# display_zm1325_rev_a.net
KiCad netlist of a schematic drawn in EAGLE
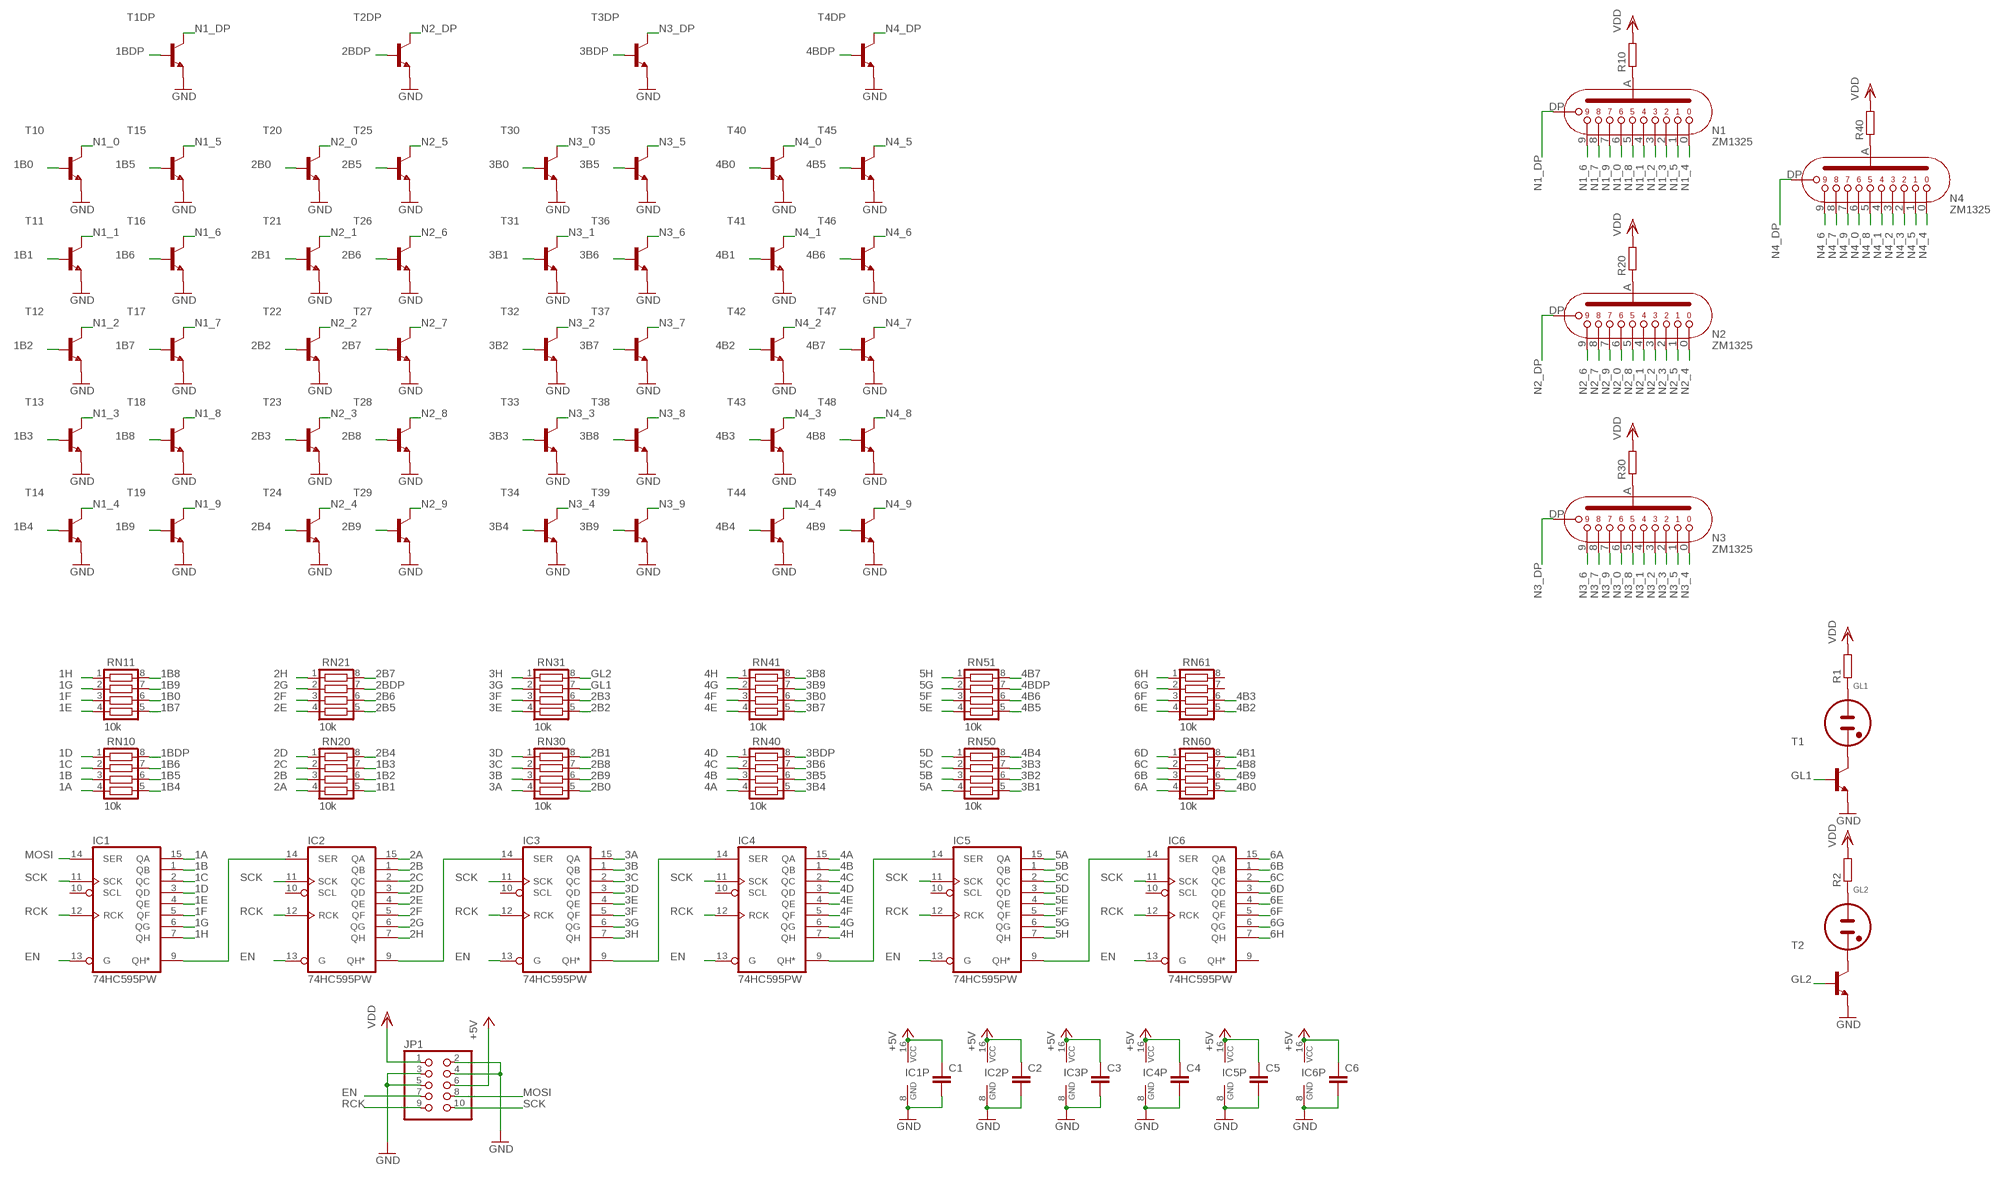
[diagram p0: schematic, sheet 1]

(export (version "E")
  (design (tool "Eeschema 10.0.6"))
  (components
    (comp (ref "C1")
      (value "C-EUC0603")
      (footprint "eagle-import:C0603")
      (libsource (lib "eagle-import") (part "C-EUC0603"))
    )
    (comp (ref "C2")
      (value "C-EUC0603")
      (footprint "eagle-import:C0603")
      (libsource (lib "eagle-import") (part "C-EUC0603"))
    )
    (comp (ref "C3")
      (value "C-EUC0603")
      (footprint "eagle-import:C0603")
      (libsource (lib "eagle-import") (part "C-EUC0603"))
    )
    (comp (ref "C4")
      (value "C-EUC0603")
      (footprint "eagle-import:C0603")
      (libsource (lib "eagle-import") (part "C-EUC0603"))
    )
    (comp (ref "C5")
      (value "C-EUC0603")
      (footprint "eagle-import:C0603")
      (libsource (lib "eagle-import") (part "C-EUC0603"))
    )
    (comp (ref "C6")
      (value "C-EUC0603")
      (footprint "eagle-import:C0603")
      (libsource (lib "eagle-import") (part "C-EUC0603"))
    )
    (comp (ref "GL1")
      (value "NE2-NEON-BULB-DRILL")
      (footprint "eagle-import:NE2-NEON-BULB-DRILL")
      (libsource (lib "eagle-import") (part "NE2-NEON-BULB-DRILL"))
    )
    (comp (ref "GL2")
      (value "NE2-NEON-BULB-DRILL")
      (footprint "eagle-import:NE2-NEON-BULB-DRILL")
      (libsource (lib "eagle-import") (part "NE2-NEON-BULB-DRILL"))
    )
    (comp (ref "IC1")
      (value "74HC595PW")
      (footprint "eagle-import:TSSOP16")
      (libsource (lib "eagle-import") (part "74595PWHC"))
    )
    (comp (ref "IC2")
      (value "74HC595PW")
      (footprint "eagle-import:TSSOP16")
      (libsource (lib "eagle-import") (part "74595PWHC"))
    )
    (comp (ref "IC3")
      (value "74HC595PW")
      (footprint "eagle-import:TSSOP16")
      (libsource (lib "eagle-import") (part "74595PWHC"))
    )
    (comp (ref "IC4")
      (value "74HC595PW")
      (footprint "eagle-import:TSSOP16")
      (libsource (lib "eagle-import") (part "74595PWHC"))
    )
    (comp (ref "IC5")
      (value "74HC595PW")
      (footprint "eagle-import:TSSOP16")
      (libsource (lib "eagle-import") (part "74595PWHC"))
    )
    (comp (ref "IC6")
      (value "74HC595PW")
      (footprint "eagle-import:TSSOP16")
      (libsource (lib "eagle-import") (part "74595PWHC"))
    )
    (comp (ref "JP1")
      (value "PINHD-2X5_2.54-SMD")
      (footprint "eagle-import:2X05SMD")
      (libsource (lib "eagle-import") (part "PINHD-2X5_2.54-SMD"))
    )
    (comp (ref "N1")
      (value "ZM1325")
      (footprint "eagle-import:ZM1325")
      (libsource (lib "eagle-import") (part "ZM1325"))
    )
    (comp (ref "N2")
      (value "ZM1325")
      (footprint "eagle-import:ZM1325")
      (libsource (lib "eagle-import") (part "ZM1325"))
    )
    (comp (ref "N3")
      (value "ZM1325")
      (footprint "eagle-import:ZM1325")
      (libsource (lib "eagle-import") (part "ZM1325"))
    )
    (comp (ref "N4")
      (value "ZM1325")
      (footprint "eagle-import:ZM1325")
      (libsource (lib "eagle-import") (part "ZM1325"))
    )
    (comp (ref "R1")
      (value "R-EU_R0603")
      (footprint "eagle-import:R0603")
      (libsource (lib "eagle-import") (part "R-EU_R0603"))
    )
    (comp (ref "R2")
      (value "R-EU_R0603")
      (footprint "eagle-import:R0603")
      (libsource (lib "eagle-import") (part "R-EU_R0603"))
    )
    (comp (ref "R10")
      (value "R-EU_R0603")
      (footprint "eagle-import:R0603")
      (libsource (lib "eagle-import") (part "R-EU_R0603"))
    )
    (comp (ref "R20")
      (value "R-EU_R0603")
      (footprint "eagle-import:R0603")
      (libsource (lib "eagle-import") (part "R-EU_R0603"))
    )
    (comp (ref "R30")
      (value "R-EU_R0603")
      (footprint "eagle-import:R0603")
      (libsource (lib "eagle-import") (part "R-EU_R0603"))
    )
    (comp (ref "R40")
      (value "R-EU_R0603")
      (footprint "eagle-import:R0603")
      (libsource (lib "eagle-import") (part "R-EU_R0603"))
    )
    (comp (ref "RN10")
      (value "10k")
      (footprint "eagle-import:CTS742C083")
      (fields (field (name "OC_FARNELL") "unknown") (field (name "OC_NEWARK") "unknown"))
      (libsource (lib "eagle-import") (part "CTS742C083"))
    )
    (comp (ref "RN11")
      (value "10k")
      (footprint "eagle-import:CTS742C083")
      (fields (field (name "OC_FARNELL") "unknown") (field (name "OC_NEWARK") "unknown"))
      (libsource (lib "eagle-import") (part "CTS742C083"))
    )
    (comp (ref "RN20")
      (value "10k")
      (footprint "eagle-import:CTS742C083")
      (fields (field (name "OC_FARNELL") "unknown") (field (name "OC_NEWARK") "unknown"))
      (libsource (lib "eagle-import") (part "CTS742C083"))
    )
    (comp (ref "RN21")
      (value "10k")
      (footprint "eagle-import:CTS742C083")
      (fields (field (name "OC_FARNELL") "unknown") (field (name "OC_NEWARK") "unknown"))
      (libsource (lib "eagle-import") (part "CTS742C083"))
    )
    (comp (ref "RN30")
      (value "10k")
      (footprint "eagle-import:CTS742C083")
      (fields (field (name "OC_FARNELL") "unknown") (field (name "OC_NEWARK") "unknown"))
      (libsource (lib "eagle-import") (part "CTS742C083"))
    )
    (comp (ref "RN31")
      (value "10k")
      (footprint "eagle-import:CTS742C083")
      (fields (field (name "OC_FARNELL") "unknown") (field (name "OC_NEWARK") "unknown"))
      (libsource (lib "eagle-import") (part "CTS742C083"))
    )
    (comp (ref "RN40")
      (value "10k")
      (footprint "eagle-import:CTS742C083")
      (fields (field (name "OC_FARNELL") "unknown") (field (name "OC_NEWARK") "unknown"))
      (libsource (lib "eagle-import") (part "CTS742C083"))
    )
    (comp (ref "RN41")
      (value "10k")
      (footprint "eagle-import:CTS742C083")
      (fields (field (name "OC_FARNELL") "unknown") (field (name "OC_NEWARK") "unknown"))
      (libsource (lib "eagle-import") (part "CTS742C083"))
    )
    (comp (ref "RN50")
      (value "10k")
      (footprint "eagle-import:CTS742C083")
      (fields (field (name "OC_FARNELL") "unknown") (field (name "OC_NEWARK") "unknown"))
      (libsource (lib "eagle-import") (part "CTS742C083"))
    )
    (comp (ref "RN51")
      (value "10k")
      (footprint "eagle-import:CTS742C083")
      (fields (field (name "OC_FARNELL") "unknown") (field (name "OC_NEWARK") "unknown"))
      (libsource (lib "eagle-import") (part "CTS742C083"))
    )
    (comp (ref "RN60")
      (value "10k")
      (footprint "eagle-import:CTS742C083")
      (fields (field (name "OC_FARNELL") "unknown") (field (name "OC_NEWARK") "unknown"))
      (libsource (lib "eagle-import") (part "CTS742C083"))
    )
    (comp (ref "RN61")
      (value "10k")
      (footprint "eagle-import:CTS742C083")
      (fields (field (name "OC_FARNELL") "unknown") (field (name "OC_NEWARK") "unknown"))
      (libsource (lib "eagle-import") (part "CTS742C083"))
    )
    (comp (ref "T1")
      (value "SMBTA42")
      (footprint "eagle-import:SOT23")
      (libsource (lib "eagle-import") (part "SMBTA42"))
    )
    (comp (ref "T1DP")
      (value "SMBTA42")
      (footprint "eagle-import:SOT23")
      (libsource (lib "eagle-import") (part "SMBTA42"))
    )
    (comp (ref "T2")
      (value "SMBTA42")
      (footprint "eagle-import:SOT23")
      (libsource (lib "eagle-import") (part "SMBTA42"))
    )
    (comp (ref "T2DP")
      (value "SMBTA42")
      (footprint "eagle-import:SOT23")
      (libsource (lib "eagle-import") (part "SMBTA42"))
    )
    (comp (ref "T3DP")
      (value "SMBTA42")
      (footprint "eagle-import:SOT23")
      (libsource (lib "eagle-import") (part "SMBTA42"))
    )
    (comp (ref "T4DP")
      (value "SMBTA42")
      (footprint "eagle-import:SOT23")
      (libsource (lib "eagle-import") (part "SMBTA42"))
    )
    (comp (ref "T10")
      (value "SMBTA42")
      (footprint "eagle-import:SOT23")
      (libsource (lib "eagle-import") (part "SMBTA42"))
    )
    (comp (ref "T11")
      (value "SMBTA42")
      (footprint "eagle-import:SOT23")
      (libsource (lib "eagle-import") (part "SMBTA42"))
    )
    (comp (ref "T12")
      (value "SMBTA42")
      (footprint "eagle-import:SOT23")
      (libsource (lib "eagle-import") (part "SMBTA42"))
    )
    (comp (ref "T13")
      (value "SMBTA42")
      (footprint "eagle-import:SOT23")
      (libsource (lib "eagle-import") (part "SMBTA42"))
    )
    (comp (ref "T14")
      (value "SMBTA42")
      (footprint "eagle-import:SOT23")
      (libsource (lib "eagle-import") (part "SMBTA42"))
    )
    (comp (ref "T15")
      (value "SMBTA42")
      (footprint "eagle-import:SOT23")
      (libsource (lib "eagle-import") (part "SMBTA42"))
    )
    (comp (ref "T16")
      (value "SMBTA42")
      (footprint "eagle-import:SOT23")
      (libsource (lib "eagle-import") (part "SMBTA42"))
    )
    (comp (ref "T17")
      (value "SMBTA42")
      (footprint "eagle-import:SOT23")
      (libsource (lib "eagle-import") (part "SMBTA42"))
    )
    (comp (ref "T18")
      (value "SMBTA42")
      (footprint "eagle-import:SOT23")
      (libsource (lib "eagle-import") (part "SMBTA42"))
    )
    (comp (ref "T19")
      (value "SMBTA42")
      (footprint "eagle-import:SOT23")
      (libsource (lib "eagle-import") (part "SMBTA42"))
    )
    (comp (ref "T20")
      (value "SMBTA42")
      (footprint "eagle-import:SOT23")
      (libsource (lib "eagle-import") (part "SMBTA42"))
    )
    (comp (ref "T21")
      (value "SMBTA42")
      (footprint "eagle-import:SOT23")
      (libsource (lib "eagle-import") (part "SMBTA42"))
    )
    (comp (ref "T22")
      (value "SMBTA42")
      (footprint "eagle-import:SOT23")
      (libsource (lib "eagle-import") (part "SMBTA42"))
    )
    (comp (ref "T23")
      (value "SMBTA42")
      (footprint "eagle-import:SOT23")
      (libsource (lib "eagle-import") (part "SMBTA42"))
    )
    (comp (ref "T24")
      (value "SMBTA42")
      (footprint "eagle-import:SOT23")
      (libsource (lib "eagle-import") (part "SMBTA42"))
    )
    (comp (ref "T25")
      (value "SMBTA42")
      (footprint "eagle-import:SOT23")
      (libsource (lib "eagle-import") (part "SMBTA42"))
    )
    (comp (ref "T26")
      (value "SMBTA42")
      (footprint "eagle-import:SOT23")
      (libsource (lib "eagle-import") (part "SMBTA42"))
    )
    (comp (ref "T27")
      (value "SMBTA42")
      (footprint "eagle-import:SOT23")
      (libsource (lib "eagle-import") (part "SMBTA42"))
    )
    (comp (ref "T28")
      (value "SMBTA42")
      (footprint "eagle-import:SOT23")
      (libsource (lib "eagle-import") (part "SMBTA42"))
    )
    (comp (ref "T29")
      (value "SMBTA42")
      (footprint "eagle-import:SOT23")
      (libsource (lib "eagle-import") (part "SMBTA42"))
    )
    (comp (ref "T30")
      (value "SMBTA42")
      (footprint "eagle-import:SOT23")
      (libsource (lib "eagle-import") (part "SMBTA42"))
    )
    (comp (ref "T31")
      (value "SMBTA42")
      (footprint "eagle-import:SOT23")
      (libsource (lib "eagle-import") (part "SMBTA42"))
    )
    (comp (ref "T32")
      (value "SMBTA42")
      (footprint "eagle-import:SOT23")
      (libsource (lib "eagle-import") (part "SMBTA42"))
    )
    (comp (ref "T33")
      (value "SMBTA42")
      (footprint "eagle-import:SOT23")
      (libsource (lib "eagle-import") (part "SMBTA42"))
    )
    (comp (ref "T34")
      (value "SMBTA42")
      (footprint "eagle-import:SOT23")
      (libsource (lib "eagle-import") (part "SMBTA42"))
    )
    (comp (ref "T35")
      (value "SMBTA42")
      (footprint "eagle-import:SOT23")
      (libsource (lib "eagle-import") (part "SMBTA42"))
    )
    (comp (ref "T36")
      (value "SMBTA42")
      (footprint "eagle-import:SOT23")
      (libsource (lib "eagle-import") (part "SMBTA42"))
    )
    (comp (ref "T37")
      (value "SMBTA42")
      (footprint "eagle-import:SOT23")
      (libsource (lib "eagle-import") (part "SMBTA42"))
    )
    (comp (ref "T38")
      (value "SMBTA42")
      (footprint "eagle-import:SOT23")
      (libsource (lib "eagle-import") (part "SMBTA42"))
    )
    (comp (ref "T39")
      (value "SMBTA42")
      (footprint "eagle-import:SOT23")
      (libsource (lib "eagle-import") (part "SMBTA42"))
    )
    (comp (ref "T40")
      (value "SMBTA42")
      (footprint "eagle-import:SOT23")
      (libsource (lib "eagle-import") (part "SMBTA42"))
    )
    (comp (ref "T41")
      (value "SMBTA42")
      (footprint "eagle-import:SOT23")
      (libsource (lib "eagle-import") (part "SMBTA42"))
    )
    (comp (ref "T42")
      (value "SMBTA42")
      (footprint "eagle-import:SOT23")
      (libsource (lib "eagle-import") (part "SMBTA42"))
    )
    (comp (ref "T43")
      (value "SMBTA42")
      (footprint "eagle-import:SOT23")
      (libsource (lib "eagle-import") (part "SMBTA42"))
    )
    (comp (ref "T44")
      (value "SMBTA42")
      (footprint "eagle-import:SOT23")
      (libsource (lib "eagle-import") (part "SMBTA42"))
    )
    (comp (ref "T45")
      (value "SMBTA42")
      (footprint "eagle-import:SOT23")
      (libsource (lib "eagle-import") (part "SMBTA42"))
    )
    (comp (ref "T46")
      (value "SMBTA42")
      (footprint "eagle-import:SOT23")
      (libsource (lib "eagle-import") (part "SMBTA42"))
    )
    (comp (ref "T47")
      (value "SMBTA42")
      (footprint "eagle-import:SOT23")
      (libsource (lib "eagle-import") (part "SMBTA42"))
    )
    (comp (ref "T48")
      (value "SMBTA42")
      (footprint "eagle-import:SOT23")
      (libsource (lib "eagle-import") (part "SMBTA42"))
    )
    (comp (ref "T49")
      (value "SMBTA42")
      (footprint "eagle-import:SOT23")
      (libsource (lib "eagle-import") (part "SMBTA42"))
    )
  )
  (nets
    (net (code "1") (name "+5V") (class "Default")
      (node (ref "C1") (pin "1") (pinfunction "1_1") (pintype "passive"))
      (node (ref "C2") (pin "1") (pinfunction "1_1") (pintype "passive"))
      (node (ref "C3") (pin "1") (pinfunction "1_1") (pintype "passive"))
      (node (ref "C4") (pin "1") (pinfunction "1_1") (pintype "passive"))
      (node (ref "C5") (pin "1") (pinfunction "1_1") (pintype "passive"))
      (node (ref "C6") (pin "1") (pinfunction "1_1") (pintype "passive"))
      (node (ref "IC1") (pin "16") (pinfunction "VCC_16") (pintype "power_in"))
      (node (ref "IC2") (pin "16") (pinfunction "VCC_16") (pintype "power_in"))
      (node (ref "IC3") (pin "16") (pinfunction "VCC_16") (pintype "power_in"))
      (node (ref "IC4") (pin "16") (pinfunction "VCC_16") (pintype "power_in"))
      (node (ref "IC5") (pin "16") (pinfunction "VCC_16") (pintype "power_in"))
      (node (ref "IC6") (pin "16") (pinfunction "VCC_16") (pintype "power_in"))
      (node (ref "JP1") (pin "6") (pinfunction "6_6") (pintype "passive"))
    )
    (net (code "2") (name "/1A") (class "Default")
      (node (ref "IC1") (pin "15") (pinfunction "QA_15") (pintype "tri_state"))
      (node (ref "RN10") (pin "4") (pinfunction "4_4") (pintype "passive"))
    )
    (net (code "3") (name "/1B") (class "Default")
      (node (ref "IC1") (pin "1") (pinfunction "QB_1") (pintype "tri_state"))
      (node (ref "RN10") (pin "3") (pinfunction "3_3") (pintype "passive"))
    )
    (net (code "4") (name "/1B0") (class "Default")
      (node (ref "RN11") (pin "6") (pinfunction "6_6") (pintype "passive"))
      (node (ref "T10") (pin "1") (pinfunction "B_1") (pintype "passive"))
    )
    (net (code "5") (name "/1B1") (class "Default")
      (node (ref "RN20") (pin "5") (pinfunction "5_5") (pintype "passive"))
      (node (ref "T11") (pin "1") (pinfunction "B_1") (pintype "passive"))
    )
    (net (code "6") (name "/1B2") (class "Default")
      (node (ref "RN20") (pin "6") (pinfunction "6_6") (pintype "passive"))
      (node (ref "T12") (pin "1") (pinfunction "B_1") (pintype "passive"))
    )
    (net (code "7") (name "/1B3") (class "Default")
      (node (ref "RN20") (pin "7") (pinfunction "7_7") (pintype "passive"))
      (node (ref "T13") (pin "1") (pinfunction "B_1") (pintype "passive"))
    )
    (net (code "8") (name "/1B4") (class "Default")
      (node (ref "RN10") (pin "5") (pinfunction "5_5") (pintype "passive"))
      (node (ref "T14") (pin "1") (pinfunction "B_1") (pintype "passive"))
    )
    (net (code "9") (name "/1B5") (class "Default")
      (node (ref "RN10") (pin "6") (pinfunction "6_6") (pintype "passive"))
      (node (ref "T15") (pin "1") (pinfunction "B_1") (pintype "passive"))
    )
    (net (code "10") (name "/1B6") (class "Default")
      (node (ref "RN10") (pin "7") (pinfunction "7_7") (pintype "passive"))
      (node (ref "T16") (pin "1") (pinfunction "B_1") (pintype "passive"))
    )
    (net (code "11") (name "/1B7") (class "Default")
      (node (ref "RN11") (pin "5") (pinfunction "5_5") (pintype "passive"))
      (node (ref "T17") (pin "1") (pinfunction "B_1") (pintype "passive"))
    )
    (net (code "12") (name "/1B8") (class "Default")
      (node (ref "RN11") (pin "8") (pinfunction "8_8") (pintype "passive"))
      (node (ref "T18") (pin "1") (pinfunction "B_1") (pintype "passive"))
    )
    (net (code "13") (name "/1B9") (class "Default")
      (node (ref "RN11") (pin "7") (pinfunction "7_7") (pintype "passive"))
      (node (ref "T19") (pin "1") (pinfunction "B_1") (pintype "passive"))
    )
    (net (code "14") (name "/1BDP") (class "Default")
      (node (ref "RN10") (pin "8") (pinfunction "8_8") (pintype "passive"))
      (node (ref "T1DP") (pin "1") (pinfunction "B_1") (pintype "passive"))
    )
    (net (code "15") (name "/1C") (class "Default")
      (node (ref "IC1") (pin "2") (pinfunction "QC_2") (pintype "tri_state"))
      (node (ref "RN10") (pin "2") (pinfunction "2_2") (pintype "passive"))
    )
    (net (code "16") (name "/1D") (class "Default")
      (node (ref "IC1") (pin "3") (pinfunction "QD_3") (pintype "tri_state"))
      (node (ref "RN10") (pin "1") (pinfunction "1_1") (pintype "passive"))
    )
    (net (code "17") (name "/1E") (class "Default")
      (node (ref "IC1") (pin "4") (pinfunction "QE_4") (pintype "tri_state"))
      (node (ref "RN11") (pin "4") (pinfunction "4_4") (pintype "passive"))
    )
    (net (code "18") (name "/1F") (class "Default")
      (node (ref "IC1") (pin "5") (pinfunction "QF_5") (pintype "tri_state"))
      (node (ref "RN11") (pin "3") (pinfunction "3_3") (pintype "passive"))
    )
    (net (code "19") (name "/1G") (class "Default")
      (node (ref "IC1") (pin "6") (pinfunction "QG_6") (pintype "tri_state"))
      (node (ref "RN11") (pin "2") (pinfunction "2_2") (pintype "passive"))
    )
    (net (code "20") (name "/1H") (class "Default")
      (node (ref "IC1") (pin "7") (pinfunction "QH_7") (pintype "tri_state"))
      (node (ref "RN11") (pin "1") (pinfunction "1_1") (pintype "passive"))
    )
    (net (code "21") (name "/2A") (class "Default")
      (node (ref "IC2") (pin "15") (pinfunction "QA_15") (pintype "tri_state"))
      (node (ref "RN20") (pin "4") (pinfunction "4_4") (pintype "passive"))
    )
    (net (code "22") (name "/2B") (class "Default")
      (node (ref "IC2") (pin "1") (pinfunction "QB_1") (pintype "tri_state"))
      (node (ref "RN20") (pin "3") (pinfunction "3_3") (pintype "passive"))
    )
    (net (code "23") (name "/2B0") (class "Default")
      (node (ref "RN30") (pin "5") (pinfunction "5_5") (pintype "passive"))
      (node (ref "T20") (pin "1") (pinfunction "B_1") (pintype "passive"))
    )
    (net (code "24") (name "/2B1") (class "Default")
      (node (ref "RN30") (pin "8") (pinfunction "8_8") (pintype "passive"))
      (node (ref "T21") (pin "1") (pinfunction "B_1") (pintype "passive"))
    )
    (net (code "25") (name "/2B2") (class "Default")
      (node (ref "RN31") (pin "5") (pinfunction "5_5") (pintype "passive"))
      (node (ref "T22") (pin "1") (pinfunction "B_1") (pintype "passive"))
    )
    (net (code "26") (name "/2B3") (class "Default")
      (node (ref "RN31") (pin "6") (pinfunction "6_6") (pintype "passive"))
      (node (ref "T23") (pin "1") (pinfunction "B_1") (pintype "passive"))
    )
    (net (code "27") (name "/2B4") (class "Default")
      (node (ref "RN20") (pin "8") (pinfunction "8_8") (pintype "passive"))
      (node (ref "T24") (pin "1") (pinfunction "B_1") (pintype "passive"))
    )
    (net (code "28") (name "/2B5") (class "Default")
      (node (ref "RN21") (pin "5") (pinfunction "5_5") (pintype "passive"))
      (node (ref "T25") (pin "1") (pinfunction "B_1") (pintype "passive"))
    )
    (net (code "29") (name "/2B6") (class "Default")
      (node (ref "RN21") (pin "6") (pinfunction "6_6") (pintype "passive"))
      (node (ref "T26") (pin "1") (pinfunction "B_1") (pintype "passive"))
    )
    (net (code "30") (name "/2B7") (class "Default")
      (node (ref "RN21") (pin "8") (pinfunction "8_8") (pintype "passive"))
      (node (ref "T27") (pin "1") (pinfunction "B_1") (pintype "passive"))
    )
    (net (code "31") (name "/2B8") (class "Default")
      (node (ref "RN30") (pin "7") (pinfunction "7_7") (pintype "passive"))
      (node (ref "T28") (pin "1") (pinfunction "B_1") (pintype "passive"))
    )
    (net (code "32") (name "/2B9") (class "Default")
      (node (ref "RN30") (pin "6") (pinfunction "6_6") (pintype "passive"))
      (node (ref "T29") (pin "1") (pinfunction "B_1") (pintype "passive"))
    )
    (net (code "33") (name "/2BDP") (class "Default")
      (node (ref "RN21") (pin "7") (pinfunction "7_7") (pintype "passive"))
      (node (ref "T2DP") (pin "1") (pinfunction "B_1") (pintype "passive"))
    )
    (net (code "34") (name "/2C") (class "Default")
      (node (ref "IC2") (pin "2") (pinfunction "QC_2") (pintype "tri_state"))
      (node (ref "RN20") (pin "2") (pinfunction "2_2") (pintype "passive"))
    )
    (net (code "35") (name "/2D") (class "Default")
      (node (ref "IC2") (pin "3") (pinfunction "QD_3") (pintype "tri_state"))
      (node (ref "RN20") (pin "1") (pinfunction "1_1") (pintype "passive"))
    )
    (net (code "36") (name "/2E") (class "Default")
      (node (ref "IC2") (pin "4") (pinfunction "QE_4") (pintype "tri_state"))
      (node (ref "RN21") (pin "4") (pinfunction "4_4") (pintype "passive"))
    )
    (net (code "37") (name "/2F") (class "Default")
      (node (ref "IC2") (pin "5") (pinfunction "QF_5") (pintype "tri_state"))
      (node (ref "RN21") (pin "3") (pinfunction "3_3") (pintype "passive"))
    )
    (net (code "38") (name "/2G") (class "Default")
      (node (ref "IC2") (pin "6") (pinfunction "QG_6") (pintype "tri_state"))
      (node (ref "RN21") (pin "2") (pinfunction "2_2") (pintype "passive"))
    )
    (net (code "39") (name "/2H") (class "Default")
      (node (ref "IC2") (pin "7") (pinfunction "QH_7") (pintype "tri_state"))
      (node (ref "RN21") (pin "1") (pinfunction "1_1") (pintype "passive"))
    )
    (net (code "40") (name "/3A") (class "Default")
      (node (ref "IC3") (pin "15") (pinfunction "QA_15") (pintype "tri_state"))
      (node (ref "RN30") (pin "4") (pinfunction "4_4") (pintype "passive"))
    )
    (net (code "41") (name "/3B") (class "Default")
      (node (ref "IC3") (pin "1") (pinfunction "QB_1") (pintype "tri_state"))
      (node (ref "RN30") (pin "3") (pinfunction "3_3") (pintype "passive"))
    )
    (net (code "42") (name "/3B0") (class "Default")
      (node (ref "RN41") (pin "6") (pinfunction "6_6") (pintype "passive"))
      (node (ref "T30") (pin "1") (pinfunction "B_1") (pintype "passive"))
    )
    (net (code "43") (name "/3B1") (class "Default")
      (node (ref "RN50") (pin "5") (pinfunction "5_5") (pintype "passive"))
      (node (ref "T31") (pin "1") (pinfunction "B_1") (pintype "passive"))
    )
    (net (code "44") (name "/3B2") (class "Default")
      (node (ref "RN50") (pin "6") (pinfunction "6_6") (pintype "passive"))
      (node (ref "T32") (pin "1") (pinfunction "B_1") (pintype "passive"))
    )
    (net (code "45") (name "/3B3") (class "Default")
      (node (ref "RN50") (pin "7") (pinfunction "7_7") (pintype "passive"))
      (node (ref "T33") (pin "1") (pinfunction "B_1") (pintype "passive"))
    )
    (net (code "46") (name "/3B4") (class "Default")
      (node (ref "RN40") (pin "5") (pinfunction "5_5") (pintype "passive"))
      (node (ref "T34") (pin "1") (pinfunction "B_1") (pintype "passive"))
    )
    (net (code "47") (name "/3B5") (class "Default")
      (node (ref "RN40") (pin "6") (pinfunction "6_6") (pintype "passive"))
      (node (ref "T35") (pin "1") (pinfunction "B_1") (pintype "passive"))
    )
    (net (code "48") (name "/3B6") (class "Default")
      (node (ref "RN40") (pin "7") (pinfunction "7_7") (pintype "passive"))
      (node (ref "T36") (pin "1") (pinfunction "B_1") (pintype "passive"))
    )
    (net (code "49") (name "/3B7") (class "Default")
      (node (ref "RN41") (pin "5") (pinfunction "5_5") (pintype "passive"))
      (node (ref "T37") (pin "1") (pinfunction "B_1") (pintype "passive"))
    )
    (net (code "50") (name "/3B8") (class "Default")
      (node (ref "RN41") (pin "8") (pinfunction "8_8") (pintype "passive"))
      (node (ref "T38") (pin "1") (pinfunction "B_1") (pintype "passive"))
    )
    (net (code "51") (name "/3B9") (class "Default")
      (node (ref "RN41") (pin "7") (pinfunction "7_7") (pintype "passive"))
      (node (ref "T39") (pin "1") (pinfunction "B_1") (pintype "passive"))
    )
    (net (code "52") (name "/3BDP") (class "Default")
      (node (ref "RN40") (pin "8") (pinfunction "8_8") (pintype "passive"))
      (node (ref "T3DP") (pin "1") (pinfunction "B_1") (pintype "passive"))
    )
    (net (code "53") (name "/3C") (class "Default")
      (node (ref "IC3") (pin "2") (pinfunction "QC_2") (pintype "tri_state"))
      (node (ref "RN30") (pin "2") (pinfunction "2_2") (pintype "passive"))
    )
    (net (code "54") (name "/3D") (class "Default")
      (node (ref "IC3") (pin "3") (pinfunction "QD_3") (pintype "tri_state"))
      (node (ref "RN30") (pin "1") (pinfunction "1_1") (pintype "passive"))
    )
    (net (code "55") (name "/3E") (class "Default")
      (node (ref "IC3") (pin "4") (pinfunction "QE_4") (pintype "tri_state"))
      (node (ref "RN31") (pin "4") (pinfunction "4_4") (pintype "passive"))
    )
    (net (code "56") (name "/3F") (class "Default")
      (node (ref "IC3") (pin "5") (pinfunction "QF_5") (pintype "tri_state"))
      (node (ref "RN31") (pin "3") (pinfunction "3_3") (pintype "passive"))
    )
    (net (code "57") (name "/3G") (class "Default")
      (node (ref "IC3") (pin "6") (pinfunction "QG_6") (pintype "tri_state"))
      (node (ref "RN31") (pin "2") (pinfunction "2_2") (pintype "passive"))
    )
    (net (code "58") (name "/3H") (class "Default")
      (node (ref "IC3") (pin "7") (pinfunction "QH_7") (pintype "tri_state"))
      (node (ref "RN31") (pin "1") (pinfunction "1_1") (pintype "passive"))
    )
    (net (code "59") (name "/4A") (class "Default")
      (node (ref "IC4") (pin "15") (pinfunction "QA_15") (pintype "tri_state"))
      (node (ref "RN40") (pin "4") (pinfunction "4_4") (pintype "passive"))
    )
    (net (code "60") (name "/4B") (class "Default")
      (node (ref "IC4") (pin "1") (pinfunction "QB_1") (pintype "tri_state"))
      (node (ref "RN40") (pin "3") (pinfunction "3_3") (pintype "passive"))
    )
    (net (code "61") (name "/4B0") (class "Default")
      (node (ref "RN60") (pin "5") (pinfunction "5_5") (pintype "passive"))
      (node (ref "T40") (pin "1") (pinfunction "B_1") (pintype "passive"))
    )
    (net (code "62") (name "/4B1") (class "Default")
      (node (ref "RN60") (pin "8") (pinfunction "8_8") (pintype "passive"))
      (node (ref "T41") (pin "1") (pinfunction "B_1") (pintype "passive"))
    )
    (net (code "63") (name "/4B2") (class "Default")
      (node (ref "RN61") (pin "5") (pinfunction "5_5") (pintype "passive"))
      (node (ref "T42") (pin "1") (pinfunction "B_1") (pintype "passive"))
    )
    (net (code "64") (name "/4B3") (class "Default")
      (node (ref "RN61") (pin "6") (pinfunction "6_6") (pintype "passive"))
      (node (ref "T43") (pin "1") (pinfunction "B_1") (pintype "passive"))
    )
    (net (code "65") (name "/4B4") (class "Default")
      (node (ref "RN50") (pin "8") (pinfunction "8_8") (pintype "passive"))
      (node (ref "T44") (pin "1") (pinfunction "B_1") (pintype "passive"))
    )
    (net (code "66") (name "/4B5") (class "Default")
      (node (ref "RN51") (pin "5") (pinfunction "5_5") (pintype "passive"))
      (node (ref "T45") (pin "1") (pinfunction "B_1") (pintype "passive"))
    )
    (net (code "67") (name "/4B6") (class "Default")
      (node (ref "RN51") (pin "6") (pinfunction "6_6") (pintype "passive"))
      (node (ref "T46") (pin "1") (pinfunction "B_1") (pintype "passive"))
    )
    (net (code "68") (name "/4B7") (class "Default")
      (node (ref "RN51") (pin "8") (pinfunction "8_8") (pintype "passive"))
      (node (ref "T47") (pin "1") (pinfunction "B_1") (pintype "passive"))
    )
    (net (code "69") (name "/4B8") (class "Default")
      (node (ref "RN60") (pin "7") (pinfunction "7_7") (pintype "passive"))
      (node (ref "T48") (pin "1") (pinfunction "B_1") (pintype "passive"))
    )
    (net (code "70") (name "/4B9") (class "Default")
      (node (ref "RN60") (pin "6") (pinfunction "6_6") (pintype "passive"))
      (node (ref "T49") (pin "1") (pinfunction "B_1") (pintype "passive"))
    )
    (net (code "71") (name "/4BDP") (class "Default")
      (node (ref "RN51") (pin "7") (pinfunction "7_7") (pintype "passive"))
      (node (ref "T4DP") (pin "1") (pinfunction "B_1") (pintype "passive"))
    )
    (net (code "72") (name "/4C") (class "Default")
      (node (ref "IC4") (pin "2") (pinfunction "QC_2") (pintype "tri_state"))
      (node (ref "RN40") (pin "2") (pinfunction "2_2") (pintype "passive"))
    )
    (net (code "73") (name "/4D") (class "Default")
      (node (ref "IC4") (pin "3") (pinfunction "QD_3") (pintype "tri_state"))
      (node (ref "RN40") (pin "1") (pinfunction "1_1") (pintype "passive"))
    )
    (net (code "74") (name "/4E") (class "Default")
      (node (ref "IC4") (pin "4") (pinfunction "QE_4") (pintype "tri_state"))
      (node (ref "RN41") (pin "4") (pinfunction "4_4") (pintype "passive"))
    )
    (net (code "75") (name "/4F") (class "Default")
      (node (ref "IC4") (pin "5") (pinfunction "QF_5") (pintype "tri_state"))
      (node (ref "RN41") (pin "3") (pinfunction "3_3") (pintype "passive"))
    )
    (net (code "76") (name "/4G") (class "Default")
      (node (ref "IC4") (pin "6") (pinfunction "QG_6") (pintype "tri_state"))
      (node (ref "RN41") (pin "2") (pinfunction "2_2") (pintype "passive"))
    )
    (net (code "77") (name "/4H") (class "Default")
      (node (ref "IC4") (pin "7") (pinfunction "QH_7") (pintype "tri_state"))
      (node (ref "RN41") (pin "1") (pinfunction "1_1") (pintype "passive"))
    )
    (net (code "78") (name "/5A") (class "Default")
      (node (ref "IC5") (pin "15") (pinfunction "QA_15") (pintype "tri_state"))
      (node (ref "RN50") (pin "4") (pinfunction "4_4") (pintype "passive"))
    )
    (net (code "79") (name "/5B") (class "Default")
      (node (ref "IC5") (pin "1") (pinfunction "QB_1") (pintype "tri_state"))
      (node (ref "RN50") (pin "3") (pinfunction "3_3") (pintype "passive"))
    )
    (net (code "80") (name "/5C") (class "Default")
      (node (ref "IC5") (pin "2") (pinfunction "QC_2") (pintype "tri_state"))
      (node (ref "RN50") (pin "2") (pinfunction "2_2") (pintype "passive"))
    )
    (net (code "81") (name "/5D") (class "Default")
      (node (ref "IC5") (pin "3") (pinfunction "QD_3") (pintype "tri_state"))
      (node (ref "RN50") (pin "1") (pinfunction "1_1") (pintype "passive"))
    )
    (net (code "82") (name "/5E") (class "Default")
      (node (ref "IC5") (pin "4") (pinfunction "QE_4") (pintype "tri_state"))
      (node (ref "RN51") (pin "4") (pinfunction "4_4") (pintype "passive"))
    )
    (net (code "83") (name "/5F") (class "Default")
      (node (ref "IC5") (pin "5") (pinfunction "QF_5") (pintype "tri_state"))
      (node (ref "RN51") (pin "3") (pinfunction "3_3") (pintype "passive"))
    )
    (net (code "84") (name "/5G") (class "Default")
      (node (ref "IC5") (pin "6") (pinfunction "QG_6") (pintype "tri_state"))
      (node (ref "RN51") (pin "2") (pinfunction "2_2") (pintype "passive"))
    )
    (net (code "85") (name "/5H") (class "Default")
      (node (ref "IC5") (pin "7") (pinfunction "QH_7") (pintype "tri_state"))
      (node (ref "RN51") (pin "1") (pinfunction "1_1") (pintype "passive"))
    )
    (net (code "86") (name "/6A") (class "Default")
      (node (ref "IC6") (pin "15") (pinfunction "QA_15") (pintype "tri_state"))
      (node (ref "RN60") (pin "4") (pinfunction "4_4") (pintype "passive"))
    )
    (net (code "87") (name "/6B") (class "Default")
      (node (ref "IC6") (pin "1") (pinfunction "QB_1") (pintype "tri_state"))
      (node (ref "RN60") (pin "3") (pinfunction "3_3") (pintype "passive"))
    )
    (net (code "88") (name "/6C") (class "Default")
      (node (ref "IC6") (pin "2") (pinfunction "QC_2") (pintype "tri_state"))
      (node (ref "RN60") (pin "2") (pinfunction "2_2") (pintype "passive"))
    )
    (net (code "89") (name "/6D") (class "Default")
      (node (ref "IC6") (pin "3") (pinfunction "QD_3") (pintype "tri_state"))
      (node (ref "RN60") (pin "1") (pinfunction "1_1") (pintype "passive"))
    )
    (net (code "90") (name "/6E") (class "Default")
      (node (ref "IC6") (pin "4") (pinfunction "QE_4") (pintype "tri_state"))
      (node (ref "RN61") (pin "4") (pinfunction "4_4") (pintype "passive"))
    )
    (net (code "91") (name "/6F") (class "Default")
      (node (ref "IC6") (pin "5") (pinfunction "QF_5") (pintype "tri_state"))
      (node (ref "RN61") (pin "3") (pinfunction "3_3") (pintype "passive"))
    )
    (net (code "92") (name "/6G") (class "Default")
      (node (ref "IC6") (pin "6") (pinfunction "QG_6") (pintype "tri_state"))
      (node (ref "RN61") (pin "2") (pinfunction "2_2") (pintype "passive"))
    )
    (net (code "93") (name "/6H") (class "Default")
      (node (ref "IC6") (pin "7") (pinfunction "QH_7") (pintype "tri_state"))
      (node (ref "RN61") (pin "1") (pinfunction "1_1") (pintype "passive"))
    )
    (net (code "94") (name "/EN") (class "Default")
      (node (ref "IC1") (pin "13") (pinfunction "G_13") (pintype "input"))
      (node (ref "IC2") (pin "13") (pinfunction "G_13") (pintype "input"))
      (node (ref "IC3") (pin "13") (pinfunction "G_13") (pintype "input"))
      (node (ref "IC4") (pin "13") (pinfunction "G_13") (pintype "input"))
      (node (ref "IC5") (pin "13") (pinfunction "G_13") (pintype "input"))
      (node (ref "IC6") (pin "13") (pinfunction "G_13") (pintype "input"))
      (node (ref "JP1") (pin "7") (pinfunction "7_7") (pintype "passive"))
    )
    (net (code "95") (name "/GL1") (class "Default")
      (node (ref "RN31") (pin "7") (pinfunction "7_7") (pintype "passive"))
      (node (ref "T1") (pin "1") (pinfunction "B_1") (pintype "passive"))
    )
    (net (code "96") (name "/GL2") (class "Default")
      (node (ref "RN31") (pin "8") (pinfunction "8_8") (pintype "passive"))
      (node (ref "T2") (pin "1") (pinfunction "B_1") (pintype "passive"))
    )
    (net (code "97") (name "/MOSI") (class "Default")
      (node (ref "IC1") (pin "14") (pinfunction "SER_14") (pintype "input"))
      (node (ref "JP1") (pin "8") (pinfunction "8_8") (pintype "passive"))
    )
    (net (code "98") (name "/N1_0") (class "Default")
      (node (ref "N1") (pin "K6") (pinfunction "6_K6") (pintype "bidirectional"))
      (node (ref "T10") (pin "3") (pinfunction "C_3") (pintype "passive"))
    )
    (net (code "99") (name "/N1_1") (class "Default")
      (node (ref "N1") (pin "K4") (pinfunction "4_K4") (pintype "bidirectional"))
      (node (ref "T11") (pin "3") (pinfunction "C_3") (pintype "passive"))
    )
    (net (code "100") (name "/N1_2") (class "Default")
      (node (ref "N1") (pin "K3") (pinfunction "3_K3") (pintype "bidirectional"))
      (node (ref "T12") (pin "3") (pinfunction "C_3") (pintype "passive"))
    )
    (net (code "101") (name "/N1_3") (class "Default")
      (node (ref "N1") (pin "K2") (pinfunction "2_K2") (pintype "bidirectional"))
      (node (ref "T13") (pin "3") (pinfunction "C_3") (pintype "passive"))
    )
    (net (code "102") (name "/N1_4") (class "Default")
      (node (ref "N1") (pin "K0") (pinfunction "0_K0") (pintype "bidirectional"))
      (node (ref "T14") (pin "3") (pinfunction "C_3") (pintype "passive"))
    )
    (net (code "103") (name "/N1_5") (class "Default")
      (node (ref "N1") (pin "K1") (pinfunction "1_K1") (pintype "bidirectional"))
      (node (ref "T15") (pin "3") (pinfunction "C_3") (pintype "passive"))
    )
    (net (code "104") (name "/N1_6") (class "Default")
      (node (ref "N1") (pin "K9") (pinfunction "9_K9") (pintype "bidirectional"))
      (node (ref "T16") (pin "3") (pinfunction "C_3") (pintype "passive"))
    )
    (net (code "105") (name "/N1_7") (class "Default")
      (node (ref "N1") (pin "K8") (pinfunction "8_K8") (pintype "bidirectional"))
      (node (ref "T17") (pin "3") (pinfunction "C_3") (pintype "passive"))
    )
    (net (code "106") (name "/N1_8") (class "Default")
      (node (ref "N1") (pin "K5") (pinfunction "5_K5") (pintype "bidirectional"))
      (node (ref "T18") (pin "3") (pinfunction "C_3") (pintype "passive"))
    )
    (net (code "107") (name "/N1_9") (class "Default")
      (node (ref "N1") (pin "K7") (pinfunction "7_K7") (pintype "bidirectional"))
      (node (ref "T19") (pin "3") (pinfunction "C_3") (pintype "passive"))
    )
    (net (code "108") (name "/N1_DP") (class "Default")
      (node (ref "N1") (pin "KDP") (pinfunction "DP_KDP") (pintype "bidirectional"))
      (node (ref "T1DP") (pin "3") (pinfunction "C_3") (pintype "passive"))
    )
    (net (code "109") (name "/N2_0") (class "Default")
      (node (ref "N2") (pin "K6") (pinfunction "6_K6") (pintype "bidirectional"))
      (node (ref "T20") (pin "3") (pinfunction "C_3") (pintype "passive"))
    )
    (net (code "110") (name "/N2_1") (class "Default")
      (node (ref "N2") (pin "K4") (pinfunction "4_K4") (pintype "bidirectional"))
      (node (ref "T21") (pin "3") (pinfunction "C_3") (pintype "passive"))
    )
    (net (code "111") (name "/N2_2") (class "Default")
      (node (ref "N2") (pin "K3") (pinfunction "3_K3") (pintype "bidirectional"))
      (node (ref "T22") (pin "3") (pinfunction "C_3") (pintype "passive"))
    )
    (net (code "112") (name "/N2_3") (class "Default")
      (node (ref "N2") (pin "K2") (pinfunction "2_K2") (pintype "bidirectional"))
      (node (ref "T23") (pin "3") (pinfunction "C_3") (pintype "passive"))
    )
    (net (code "113") (name "/N2_4") (class "Default")
      (node (ref "N2") (pin "K0") (pinfunction "0_K0") (pintype "bidirectional"))
      (node (ref "T24") (pin "3") (pinfunction "C_3") (pintype "passive"))
    )
    (net (code "114") (name "/N2_5") (class "Default")
      (node (ref "N2") (pin "K1") (pinfunction "1_K1") (pintype "bidirectional"))
      (node (ref "T25") (pin "3") (pinfunction "C_3") (pintype "passive"))
    )
    (net (code "115") (name "/N2_6") (class "Default")
      (node (ref "N2") (pin "K9") (pinfunction "9_K9") (pintype "bidirectional"))
      (node (ref "T26") (pin "3") (pinfunction "C_3") (pintype "passive"))
    )
    (net (code "116") (name "/N2_7") (class "Default")
      (node (ref "N2") (pin "K8") (pinfunction "8_K8") (pintype "bidirectional"))
      (node (ref "T27") (pin "3") (pinfunction "C_3") (pintype "passive"))
    )
    (net (code "117") (name "/N2_8") (class "Default")
      (node (ref "N2") (pin "K5") (pinfunction "5_K5") (pintype "bidirectional"))
      (node (ref "T28") (pin "3") (pinfunction "C_3") (pintype "passive"))
    )
    (net (code "118") (name "/N2_9") (class "Default")
      (node (ref "N2") (pin "K7") (pinfunction "7_K7") (pintype "bidirectional"))
      (node (ref "T29") (pin "3") (pinfunction "C_3") (pintype "passive"))
    )
    (net (code "119") (name "/N2_DP") (class "Default")
      (node (ref "N2") (pin "KDP") (pinfunction "DP_KDP") (pintype "bidirectional"))
      (node (ref "T2DP") (pin "3") (pinfunction "C_3") (pintype "passive"))
    )
    (net (code "120") (name "/N3_0") (class "Default")
      (node (ref "N3") (pin "K6") (pinfunction "6_K6") (pintype "bidirectional"))
      (node (ref "T30") (pin "3") (pinfunction "C_3") (pintype "passive"))
    )
    (net (code "121") (name "/N3_1") (class "Default")
      (node (ref "N3") (pin "K4") (pinfunction "4_K4") (pintype "bidirectional"))
      (node (ref "T31") (pin "3") (pinfunction "C_3") (pintype "passive"))
    )
    (net (code "122") (name "/N3_2") (class "Default")
      (node (ref "N3") (pin "K3") (pinfunction "3_K3") (pintype "bidirectional"))
      (node (ref "T32") (pin "3") (pinfunction "C_3") (pintype "passive"))
    )
    (net (code "123") (name "/N3_3") (class "Default")
      (node (ref "N3") (pin "K2") (pinfunction "2_K2") (pintype "bidirectional"))
      (node (ref "T33") (pin "3") (pinfunction "C_3") (pintype "passive"))
    )
    (net (code "124") (name "/N3_4") (class "Default")
      (node (ref "N3") (pin "K0") (pinfunction "0_K0") (pintype "bidirectional"))
      (node (ref "T34") (pin "3") (pinfunction "C_3") (pintype "passive"))
    )
    (net (code "125") (name "/N3_5") (class "Default")
      (node (ref "N3") (pin "K1") (pinfunction "1_K1") (pintype "bidirectional"))
      (node (ref "T35") (pin "3") (pinfunction "C_3") (pintype "passive"))
    )
    (net (code "126") (name "/N3_6") (class "Default")
      (node (ref "N3") (pin "K9") (pinfunction "9_K9") (pintype "bidirectional"))
      (node (ref "T36") (pin "3") (pinfunction "C_3") (pintype "passive"))
    )
    (net (code "127") (name "/N3_7") (class "Default")
      (node (ref "N3") (pin "K8") (pinfunction "8_K8") (pintype "bidirectional"))
      (node (ref "T37") (pin "3") (pinfunction "C_3") (pintype "passive"))
    )
    (net (code "128") (name "/N3_8") (class "Default")
      (node (ref "N3") (pin "K5") (pinfunction "5_K5") (pintype "bidirectional"))
      (node (ref "T38") (pin "3") (pinfunction "C_3") (pintype "passive"))
    )
    (net (code "129") (name "/N3_9") (class "Default")
      (node (ref "N3") (pin "K7") (pinfunction "7_K7") (pintype "bidirectional"))
      (node (ref "T39") (pin "3") (pinfunction "C_3") (pintype "passive"))
    )
    (net (code "130") (name "/N3_DP") (class "Default")
      (node (ref "N3") (pin "KDP") (pinfunction "DP_KDP") (pintype "bidirectional"))
      (node (ref "T3DP") (pin "3") (pinfunction "C_3") (pintype "passive"))
    )
    (net (code "131") (name "/N4_0") (class "Default")
      (node (ref "N4") (pin "K6") (pinfunction "6_K6") (pintype "bidirectional"))
      (node (ref "T40") (pin "3") (pinfunction "C_3") (pintype "passive"))
    )
    (net (code "132") (name "/N4_1") (class "Default")
      (node (ref "N4") (pin "K4") (pinfunction "4_K4") (pintype "bidirectional"))
      (node (ref "T41") (pin "3") (pinfunction "C_3") (pintype "passive"))
    )
    (net (code "133") (name "/N4_2") (class "Default")
      (node (ref "N4") (pin "K3") (pinfunction "3_K3") (pintype "bidirectional"))
      (node (ref "T42") (pin "3") (pinfunction "C_3") (pintype "passive"))
    )
    (net (code "134") (name "/N4_3") (class "Default")
      (node (ref "N4") (pin "K2") (pinfunction "2_K2") (pintype "bidirectional"))
      (node (ref "T43") (pin "3") (pinfunction "C_3") (pintype "passive"))
    )
    (net (code "135") (name "/N4_4") (class "Default")
      (node (ref "N4") (pin "K0") (pinfunction "0_K0") (pintype "bidirectional"))
      (node (ref "T44") (pin "3") (pinfunction "C_3") (pintype "passive"))
    )
    (net (code "136") (name "/N4_5") (class "Default")
      (node (ref "N4") (pin "K1") (pinfunction "1_K1") (pintype "bidirectional"))
      (node (ref "T45") (pin "3") (pinfunction "C_3") (pintype "passive"))
    )
    (net (code "137") (name "/N4_6") (class "Default")
      (node (ref "N4") (pin "K9") (pinfunction "9_K9") (pintype "bidirectional"))
      (node (ref "T46") (pin "3") (pinfunction "C_3") (pintype "passive"))
    )
    (net (code "138") (name "/N4_7") (class "Default")
      (node (ref "N4") (pin "K8") (pinfunction "8_K8") (pintype "bidirectional"))
      (node (ref "T47") (pin "3") (pinfunction "C_3") (pintype "passive"))
    )
    (net (code "139") (name "/N4_8") (class "Default")
      (node (ref "N4") (pin "K5") (pinfunction "5_K5") (pintype "bidirectional"))
      (node (ref "T48") (pin "3") (pinfunction "C_3") (pintype "passive"))
    )
    (net (code "140") (name "/N4_9") (class "Default")
      (node (ref "N4") (pin "K7") (pinfunction "7_K7") (pintype "bidirectional"))
      (node (ref "T49") (pin "3") (pinfunction "C_3") (pintype "passive"))
    )
    (net (code "141") (name "/N4_DP") (class "Default")
      (node (ref "N4") (pin "KDP") (pinfunction "DP_KDP") (pintype "bidirectional"))
      (node (ref "T4DP") (pin "3") (pinfunction "C_3") (pintype "passive"))
    )
    (net (code "142") (name "/RCK") (class "Default")
      (node (ref "IC1") (pin "12") (pinfunction "RCK_12") (pintype "input"))
      (node (ref "IC2") (pin "12") (pinfunction "RCK_12") (pintype "input"))
      (node (ref "IC3") (pin "12") (pinfunction "RCK_12") (pintype "input"))
      (node (ref "IC4") (pin "12") (pinfunction "RCK_12") (pintype "input"))
      (node (ref "IC5") (pin "12") (pinfunction "RCK_12") (pintype "input"))
      (node (ref "IC6") (pin "12") (pinfunction "RCK_12") (pintype "input"))
      (node (ref "JP1") (pin "9") (pinfunction "9_9") (pintype "passive"))
    )
    (net (code "143") (name "/SCK") (class "Default")
      (node (ref "IC1") (pin "11") (pinfunction "SCK_11") (pintype "input"))
      (node (ref "IC2") (pin "11") (pinfunction "SCK_11") (pintype "input"))
      (node (ref "IC3") (pin "11") (pinfunction "SCK_11") (pintype "input"))
      (node (ref "IC4") (pin "11") (pinfunction "SCK_11") (pintype "input"))
      (node (ref "IC5") (pin "11") (pinfunction "SCK_11") (pintype "input"))
      (node (ref "IC6") (pin "11") (pinfunction "SCK_11") (pintype "input"))
      (node (ref "JP1") (pin "10") (pinfunction "10_10") (pintype "passive"))
    )
    (net (code "144") (name "GND") (class "Default")
      (node (ref "C1") (pin "2") (pinfunction "2_2") (pintype "passive"))
      (node (ref "C2") (pin "2") (pinfunction "2_2") (pintype "passive"))
      (node (ref "C3") (pin "2") (pinfunction "2_2") (pintype "passive"))
      (node (ref "C4") (pin "2") (pinfunction "2_2") (pintype "passive"))
      (node (ref "C5") (pin "2") (pinfunction "2_2") (pintype "passive"))
      (node (ref "C6") (pin "2") (pinfunction "2_2") (pintype "passive"))
      (node (ref "IC1") (pin "8") (pinfunction "GND_8") (pintype "power_in"))
      (node (ref "IC2") (pin "8") (pinfunction "GND_8") (pintype "power_in"))
      (node (ref "IC3") (pin "8") (pinfunction "GND_8") (pintype "power_in"))
      (node (ref "IC4") (pin "8") (pinfunction "GND_8") (pintype "power_in"))
      (node (ref "IC5") (pin "8") (pinfunction "GND_8") (pintype "power_in"))
      (node (ref "IC6") (pin "8") (pinfunction "GND_8") (pintype "power_in"))
      (node (ref "JP1") (pin "2") (pinfunction "2_2") (pintype "passive"))
      (node (ref "JP1") (pin "3") (pinfunction "3_3") (pintype "passive"))
      (node (ref "JP1") (pin "4") (pinfunction "4_4") (pintype "passive"))
      (node (ref "JP1") (pin "5") (pinfunction "5_5") (pintype "passive"))
      (node (ref "T1") (pin "2") (pinfunction "E_2") (pintype "passive"))
      (node (ref "T10") (pin "2") (pinfunction "E_2") (pintype "passive"))
      (node (ref "T11") (pin "2") (pinfunction "E_2") (pintype "passive"))
      (node (ref "T12") (pin "2") (pinfunction "E_2") (pintype "passive"))
      (node (ref "T13") (pin "2") (pinfunction "E_2") (pintype "passive"))
      (node (ref "T14") (pin "2") (pinfunction "E_2") (pintype "passive"))
      (node (ref "T15") (pin "2") (pinfunction "E_2") (pintype "passive"))
      (node (ref "T16") (pin "2") (pinfunction "E_2") (pintype "passive"))
      (node (ref "T17") (pin "2") (pinfunction "E_2") (pintype "passive"))
      (node (ref "T18") (pin "2") (pinfunction "E_2") (pintype "passive"))
      (node (ref "T19") (pin "2") (pinfunction "E_2") (pintype "passive"))
      (node (ref "T1DP") (pin "2") (pinfunction "E_2") (pintype "passive"))
      (node (ref "T2") (pin "2") (pinfunction "E_2") (pintype "passive"))
      (node (ref "T20") (pin "2") (pinfunction "E_2") (pintype "passive"))
      (node (ref "T21") (pin "2") (pinfunction "E_2") (pintype "passive"))
      (node (ref "T22") (pin "2") (pinfunction "E_2") (pintype "passive"))
      (node (ref "T23") (pin "2") (pinfunction "E_2") (pintype "passive"))
      (node (ref "T24") (pin "2") (pinfunction "E_2") (pintype "passive"))
      (node (ref "T25") (pin "2") (pinfunction "E_2") (pintype "passive"))
      (node (ref "T26") (pin "2") (pinfunction "E_2") (pintype "passive"))
      (node (ref "T27") (pin "2") (pinfunction "E_2") (pintype "passive"))
      (node (ref "T28") (pin "2") (pinfunction "E_2") (pintype "passive"))
      (node (ref "T29") (pin "2") (pinfunction "E_2") (pintype "passive"))
      (node (ref "T2DP") (pin "2") (pinfunction "E_2") (pintype "passive"))
      (node (ref "T30") (pin "2") (pinfunction "E_2") (pintype "passive"))
      (node (ref "T31") (pin "2") (pinfunction "E_2") (pintype "passive"))
      (node (ref "T32") (pin "2") (pinfunction "E_2") (pintype "passive"))
      (node (ref "T33") (pin "2") (pinfunction "E_2") (pintype "passive"))
      (node (ref "T34") (pin "2") (pinfunction "E_2") (pintype "passive"))
      (node (ref "T35") (pin "2") (pinfunction "E_2") (pintype "passive"))
      (node (ref "T36") (pin "2") (pinfunction "E_2") (pintype "passive"))
      (node (ref "T37") (pin "2") (pinfunction "E_2") (pintype "passive"))
      (node (ref "T38") (pin "2") (pinfunction "E_2") (pintype "passive"))
      (node (ref "T39") (pin "2") (pinfunction "E_2") (pintype "passive"))
      (node (ref "T3DP") (pin "2") (pinfunction "E_2") (pintype "passive"))
      (node (ref "T40") (pin "2") (pinfunction "E_2") (pintype "passive"))
      (node (ref "T41") (pin "2") (pinfunction "E_2") (pintype "passive"))
      (node (ref "T42") (pin "2") (pinfunction "E_2") (pintype "passive"))
      (node (ref "T43") (pin "2") (pinfunction "E_2") (pintype "passive"))
      (node (ref "T44") (pin "2") (pinfunction "E_2") (pintype "passive"))
      (node (ref "T45") (pin "2") (pinfunction "E_2") (pintype "passive"))
      (node (ref "T46") (pin "2") (pinfunction "E_2") (pintype "passive"))
      (node (ref "T47") (pin "2") (pinfunction "E_2") (pintype "passive"))
      (node (ref "T48") (pin "2") (pinfunction "E_2") (pintype "passive"))
      (node (ref "T49") (pin "2") (pinfunction "E_2") (pintype "passive"))
      (node (ref "T4DP") (pin "2") (pinfunction "E_2") (pintype "passive"))
    )
    (net (code "145") (name "Net-(GL1-A)") (class "Default")
      (node (ref "GL1") (pin "1") (pinfunction "A_1") (pintype "passive"))
      (node (ref "R1") (pin "1") (pinfunction "1_1") (pintype "passive"))
    )
    (net (code "146") (name "Net-(GL1-A1)") (class "Default")
      (node (ref "GL1") (pin "2") (pinfunction "A1_2") (pintype "passive"))
      (node (ref "T1") (pin "3") (pinfunction "C_3") (pintype "passive"))
    )
    (net (code "147") (name "Net-(GL2-A)") (class "Default")
      (node (ref "GL2") (pin "1") (pinfunction "A_1") (pintype "passive"))
      (node (ref "R2") (pin "1") (pinfunction "1_1") (pintype "passive"))
    )
    (net (code "148") (name "Net-(GL2-A1)") (class "Default")
      (node (ref "GL2") (pin "2") (pinfunction "A1_2") (pintype "passive"))
      (node (ref "T2") (pin "3") (pinfunction "C_3") (pintype "passive"))
    )
    (net (code "149") (name "Net-(IC1A-QH*)") (class "Default")
      (node (ref "IC1") (pin "9") (pinfunction "QH*_9") (pintype "tri_state"))
      (node (ref "IC2") (pin "14") (pinfunction "SER_14") (pintype "input"))
    )
    (net (code "150") (name "Net-(IC2A-QH*)") (class "Default")
      (node (ref "IC2") (pin "9") (pinfunction "QH*_9") (pintype "tri_state"))
      (node (ref "IC3") (pin "14") (pinfunction "SER_14") (pintype "input"))
    )
    (net (code "151") (name "Net-(IC3A-QH*)") (class "Default")
      (node (ref "IC3") (pin "9") (pinfunction "QH*_9") (pintype "tri_state"))
      (node (ref "IC4") (pin "14") (pinfunction "SER_14") (pintype "input"))
    )
    (net (code "152") (name "Net-(IC4A-QH*)") (class "Default")
      (node (ref "IC4") (pin "9") (pinfunction "QH*_9") (pintype "tri_state"))
      (node (ref "IC5") (pin "14") (pinfunction "SER_14") (pintype "input"))
    )
    (net (code "153") (name "Net-(IC5A-QH*)") (class "Default")
      (node (ref "IC5") (pin "9") (pinfunction "QH*_9") (pintype "tri_state"))
      (node (ref "IC6") (pin "14") (pinfunction "SER_14") (pintype "input"))
    )
    (net (code "154") (name "Net-(N1-PadA)") (class "Default")
      (node (ref "N1") (pin "A") (pinfunction "A_A") (pintype "bidirectional"))
      (node (ref "R10") (pin "1") (pinfunction "1_1") (pintype "passive"))
    )
    (net (code "155") (name "Net-(N2-PadA)") (class "Default")
      (node (ref "N2") (pin "A") (pinfunction "A_A") (pintype "bidirectional"))
      (node (ref "R20") (pin "1") (pinfunction "1_1") (pintype "passive"))
    )
    (net (code "156") (name "Net-(N3-PadA)") (class "Default")
      (node (ref "N3") (pin "A") (pinfunction "A_A") (pintype "bidirectional"))
      (node (ref "R30") (pin "1") (pinfunction "1_1") (pintype "passive"))
    )
    (net (code "157") (name "Net-(N4-PadA)") (class "Default")
      (node (ref "N4") (pin "A") (pinfunction "A_A") (pintype "bidirectional"))
      (node (ref "R40") (pin "1") (pinfunction "1_1") (pintype "passive"))
    )
    (net (code "158") (name "VDD") (class "Default")
      (node (ref "JP1") (pin "1") (pinfunction "1_1") (pintype "passive"))
      (node (ref "R1") (pin "2") (pinfunction "2_2") (pintype "passive"))
      (node (ref "R10") (pin "2") (pinfunction "2_2") (pintype "passive"))
      (node (ref "R2") (pin "2") (pinfunction "2_2") (pintype "passive"))
      (node (ref "R20") (pin "2") (pinfunction "2_2") (pintype "passive"))
      (node (ref "R30") (pin "2") (pinfunction "2_2") (pintype "passive"))
      (node (ref "R40") (pin "2") (pinfunction "2_2") (pintype "passive"))
    )
    (net (code "159") (name "unconnected-(IC1A-SCL-Pad10)") (class "Default")
      (node (ref "IC1") (pin "10") (pinfunction "SCL_10") (pintype "input"))
    )
    (net (code "160") (name "unconnected-(IC2A-SCL-Pad10)") (class "Default")
      (node (ref "IC2") (pin "10") (pinfunction "SCL_10") (pintype "input"))
    )
    (net (code "161") (name "unconnected-(IC3A-SCL-Pad10)") (class "Default")
      (node (ref "IC3") (pin "10") (pinfunction "SCL_10") (pintype "input"))
    )
    (net (code "162") (name "unconnected-(IC4A-SCL-Pad10)") (class "Default")
      (node (ref "IC4") (pin "10") (pinfunction "SCL_10") (pintype "input"))
    )
    (net (code "163") (name "unconnected-(IC5A-SCL-Pad10)") (class "Default")
      (node (ref "IC5") (pin "10") (pinfunction "SCL_10") (pintype "input"))
    )
    (net (code "164") (name "unconnected-(IC6A-QH*-Pad9)") (class "Default")
      (node (ref "IC6") (pin "9") (pinfunction "QH*_9") (pintype "tri_state"))
    )
    (net (code "165") (name "unconnected-(IC6A-SCL-Pad10)") (class "Default")
      (node (ref "IC6") (pin "10") (pinfunction "SCL_10") (pintype "input"))
    )
    (net (code "166") (name "unconnected-(RN61-Pad7)") (class "Default")
      (node (ref "RN61") (pin "7") (pinfunction "7_7") (pintype "passive"))
    )
    (net (code "167") (name "unconnected-(RN61-Pad8)") (class "Default")
      (node (ref "RN61") (pin "8") (pinfunction "8_8") (pintype "passive"))
    )
  )
)
